# Lab6.net
KiCad netlist of a schematic drawn in EAGLE
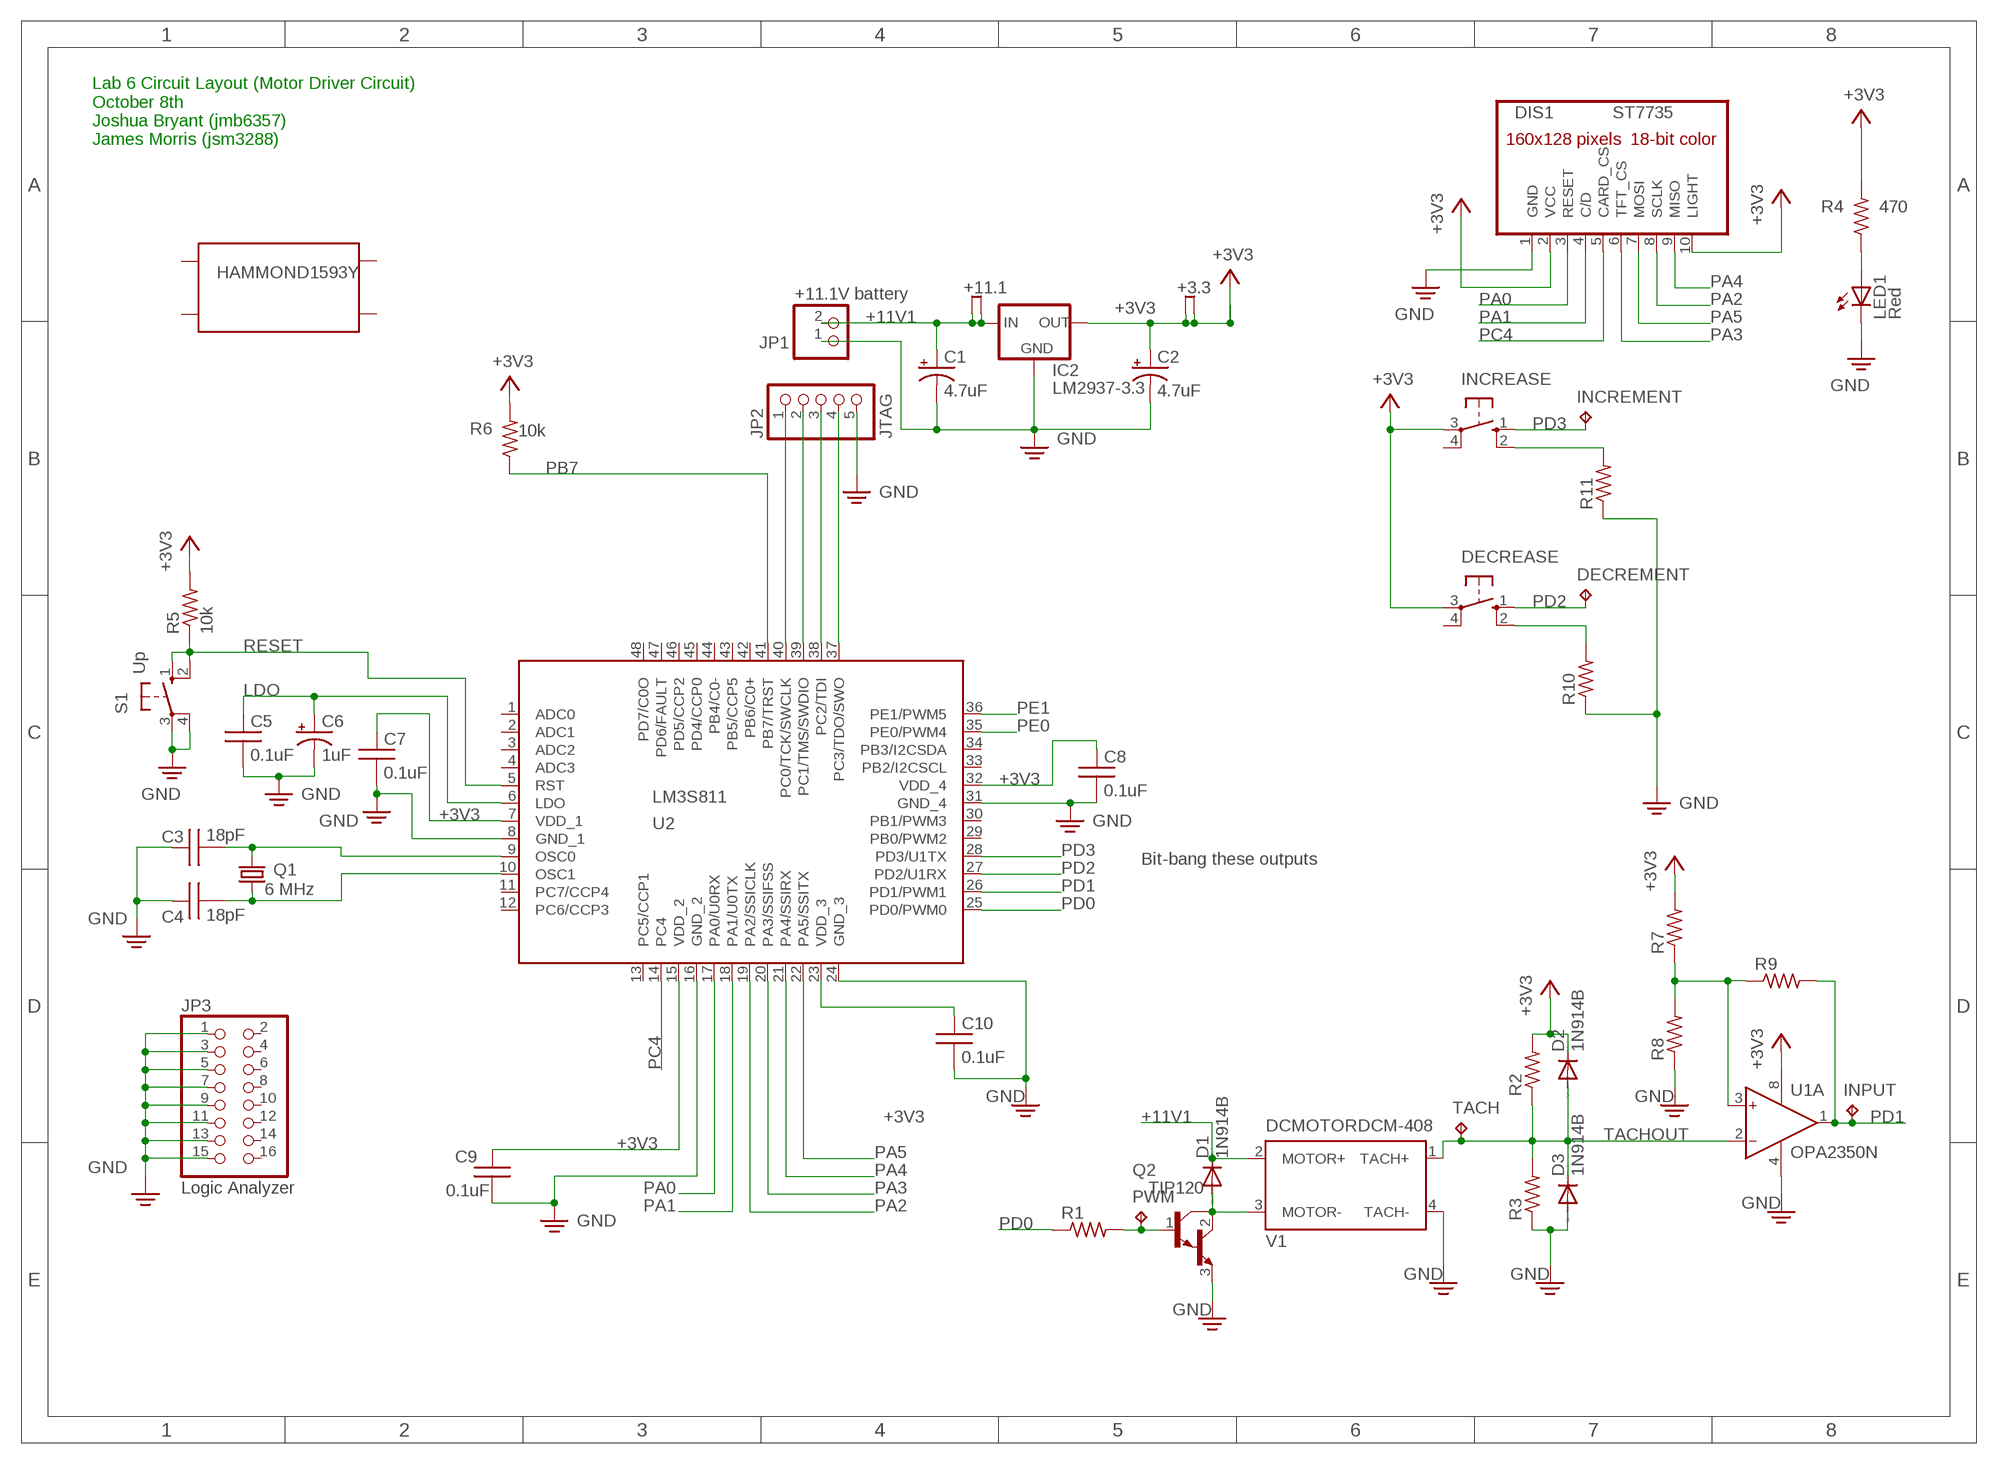
[diagram p0: schematic, sheet 1]

(export (version "E")
  (design (tool "Eeschema 10.0.6"))
  (components
    (comp (ref "+3.3")
      (value "TP2")
      (footprint "eagle-import:TP2")
      (libsource (lib "eagle-import") (part "TP2"))
    )
    (comp (ref "+11.1")
      (value "TP2")
      (footprint "eagle-import:TP2")
      (libsource (lib "eagle-import") (part "TP2"))
    )
    (comp (ref "C1")
      (value "4.7uF")
      (footprint "eagle-import:CAP200MILPOLARIZED")
      (libsource (lib "eagle-import") (part "CAPACITOR_POLARIZEDE5-6"))
    )
    (comp (ref "C2")
      (value "4.7uF")
      (footprint "eagle-import:CAP200MILPOLARIZED")
      (libsource (lib "eagle-import") (part "CAPACITOR_POLARIZEDE5-6"))
    )
    (comp (ref "C3")
      (value "18pF")
      (footprint "eagle-import:CAP100MIL")
      (libsource (lib "eagle-import") (part "CAPACITOR025-024X044"))
    )
    (comp (ref "C4")
      (value "18pF")
      (footprint "eagle-import:CAP100MIL")
      (libsource (lib "eagle-import") (part "CAPACITOR025-024X044"))
    )
    (comp (ref "C5")
      (value "0.1uF")
      (footprint "eagle-import:CAP100MIL")
      (libsource (lib "eagle-import") (part "CAPACITOR025-024X044"))
    )
    (comp (ref "C6")
      (value "1uF")
      (footprint "eagle-import:CAP200MILPOLARIZED")
      (libsource (lib "eagle-import") (part "CAPACITOR_POLARIZEDE5-6"))
    )
    (comp (ref "C7")
      (value "0.1uF")
      (footprint "eagle-import:CAP100MIL")
      (libsource (lib "eagle-import") (part "CAPACITOR025-024X044"))
    )
    (comp (ref "C8")
      (value "0.1uF")
      (footprint "eagle-import:CAP100MIL")
      (libsource (lib "eagle-import") (part "CAPACITOR025-024X044"))
    )
    (comp (ref "C9")
      (value "0.1uF")
      (footprint "eagle-import:CAP100MIL")
      (libsource (lib "eagle-import") (part "CAPACITOR025-024X044"))
    )
    (comp (ref "C10")
      (value "0.1uF")
      (footprint "eagle-import:CAP100MIL")
      (libsource (lib "eagle-import") (part "CAPACITOR025-024X044"))
    )
    (comp (ref "D1")
      (value "1N914B")
      (footprint "eagle-import:DO35-7")
      (libsource (lib "eagle-import") (part "1N914B"))
    )
    (comp (ref "D2")
      (value "1N914B")
      (footprint "eagle-import:DO35-7")
      (libsource (lib "eagle-import") (part "1N914B"))
    )
    (comp (ref "D3")
      (value "1N914B")
      (footprint "eagle-import:DO35-7")
      (libsource (lib "eagle-import") (part "1N914B"))
    )
    (comp (ref "DECREASE")
      (value "B3F-1052")
      (footprint "eagle-import:B3F-10XX")
      (fields (field (name "MPN") "B3F-1000"))
      (libsource (lib "eagle-import") (part "B3F-1052"))
    )
    (comp (ref "DECREMENT")
      (value "TP_KEYSTONE500X")
      (footprint "eagle-import:P1.1MM")
      (libsource (lib "eagle-import") (part "TP_KEYSTONE500X"))
    )
    (comp (ref "DIS1")
      (value "ST7735")
      (footprint "eagle-import:ST7735")
      (libsource (lib "eagle-import") (part "ST7735"))
    )
    (comp (ref "IC2")
      (value "LM2937-3.3")
      (footprint "eagle-import:78XXS")
      (libsource (lib "eagle-import") (part "78XXS"))
    )
    (comp (ref "INCREASE")
      (value "B3F-1052")
      (footprint "eagle-import:B3F-10XX")
      (fields (field (name "MPN") "B3F-1000"))
      (libsource (lib "eagle-import") (part "B3F-1052"))
    )
    (comp (ref "INCREMENT")
      (value "TP_KEYSTONE500X")
      (footprint "eagle-import:P1.1MM")
      (libsource (lib "eagle-import") (part "TP_KEYSTONE500X"))
    )
    (comp (ref "INPUT")
      (value "TP_KEYSTONE500X")
      (footprint "eagle-import:P1.1MM")
      (libsource (lib "eagle-import") (part "TP_KEYSTONE500X"))
    )
    (comp (ref "JP1")
      (value "+11.1V battery")
      (footprint "eagle-import:1X02")
      (libsource (lib "eagle-import") (part "PINHD-1X2"))
    )
    (comp (ref "JP2")
      (value "JTAG")
      (footprint "eagle-import:1X05")
      (libsource (lib "eagle-import") (part "PINHD-1X5"))
    )
    (comp (ref "JP3")
      (value "Logic Analyzer")
      (footprint "eagle-import:2X08_90")
      (libsource (lib "eagle-import") (part "PINHD-2X8/90"))
    )
    (comp (ref "LED1")
      (value "Red")
      (footprint "eagle-import:LED5MM")
      (libsource (lib "eagle-import") (part "LED5MM"))
    )
    (comp (ref "PWM")
      (value "TP_KEYSTONE500X")
      (footprint "eagle-import:P1.1MM")
      (libsource (lib "eagle-import") (part "TP_KEYSTONE500X"))
    )
    (comp (ref "Q1")
      (value "6 MHz")
      (footprint "eagle-import:HC49_S")
      (libsource (lib "eagle-import") (part "CRYSTALHC49S"))
    )
    (comp (ref "Q2")
      (value "TIP120")
      (footprint "eagle-import:TO220")
      (libsource (lib "eagle-import") (part "TIP120"))
    )
    (comp (ref "R1")
      (value "RESISTOR0204/7")
      (footprint "eagle-import:RES300MIL")
      (libsource (lib "eagle-import") (part "RESISTOR0204/7"))
    )
    (comp (ref "R2")
      (value "RESISTOR0204/7")
      (footprint "eagle-import:RES300MIL")
      (libsource (lib "eagle-import") (part "RESISTOR0204/7"))
    )
    (comp (ref "R3")
      (value "RESISTOR0204/7")
      (footprint "eagle-import:RES300MIL")
      (libsource (lib "eagle-import") (part "RESISTOR0204/7"))
    )
    (comp (ref "R4")
      (value "470")
      (footprint "eagle-import:RES200MIL")
      (libsource (lib "eagle-import") (part "RESISTOR0204/5"))
    )
    (comp (ref "R5")
      (value "10k")
      (footprint "eagle-import:RES200MIL")
      (libsource (lib "eagle-import") (part "RESISTOR0204/5"))
    )
    (comp (ref "R6")
      (value "10k")
      (footprint "eagle-import:RES200MIL")
      (libsource (lib "eagle-import") (part "RESISTOR0204/5"))
    )
    (comp (ref "R7")
      (value "RESISTOR0204/7")
      (footprint "eagle-import:RES300MIL")
      (libsource (lib "eagle-import") (part "RESISTOR0204/7"))
    )
    (comp (ref "R8")
      (value "RESISTOR0204/7")
      (footprint "eagle-import:RES300MIL")
      (libsource (lib "eagle-import") (part "RESISTOR0204/7"))
    )
    (comp (ref "R9")
      (value "RESISTOR0204/7")
      (footprint "eagle-import:RES300MIL")
      (libsource (lib "eagle-import") (part "RESISTOR0204/7"))
    )
    (comp (ref "R10")
      (value "RESISTOR0204/7")
      (footprint "eagle-import:RES300MIL")
      (libsource (lib "eagle-import") (part "RESISTOR0204/7"))
    )
    (comp (ref "R11")
      (value "RESISTOR0204/7")
      (footprint "eagle-import:RES300MIL")
      (libsource (lib "eagle-import") (part "RESISTOR0204/7"))
    )
    (comp (ref "S1")
      (value "Up")
      (footprint "eagle-import:B3F-10XX")
      (fields (field (name "MPN") "B3F-1000"))
      (libsource (lib "eagle-import") (part "B3F-1052"))
    )
    (comp (ref "TACH")
      (value "TP_KEYSTONE500X")
      (footprint "eagle-import:P1.1MM")
      (libsource (lib "eagle-import") (part "TP_KEYSTONE500X"))
    )
    (comp (ref "U$1")
      (value "HAMMOND1593Y")
      (footprint "eagle-import:HAMMOND1593Y")
      (libsource (lib "eagle-import") (part "HAMMOND1593Y"))
    )
    (comp (ref "U1")
      (value "OPA2350N")
      (footprint "eagle-import:DIL08")
      (libsource (lib "eagle-import") (part "OPA2350N"))
    )
    (comp (ref "U2")
      (value "LM3S811")
      (footprint "eagle-import:LQFP48-7X7")
      (libsource (lib "eagle-import") (part "LM3S811"))
    )
    (comp (ref "V1")
      (value "DCMOTORDCM-408")
      (footprint "eagle-import:DCMOTOR")
      (libsource (lib "eagle-import") (part "DCMOTORDCM-408"))
    )
  )
  (nets
    (net (code "1") (name "+3V3") (class "Default")
      (node (ref "+3.3") (pin "MP") (pinfunction "TPA_MP") (pintype "passive"))
      (node (ref "+3.3") (pin "MP1") (pinfunction "TPB_MP1") (pintype "passive"))
      (node (ref "C10") (pin "1") (pinfunction "1_1") (pintype "passive"))
      (node (ref "C2") (pin "+") (pinfunction "+_+") (pintype "passive"))
      (node (ref "C7") (pin "1") (pinfunction "1_1") (pintype "passive"))
      (node (ref "C8") (pin "1") (pinfunction "1_1") (pintype "passive"))
      (node (ref "C9") (pin "1") (pinfunction "1_1") (pintype "passive"))
      (node (ref "D2") (pin "C") (pinfunction "C_C") (pintype "passive"))
      (node (ref "DECREASE") (pin "3") (pinfunction "P_3") (pintype "passive"))
      (node (ref "DIS1") (pin "10") (pinfunction "LIGHT_10") (pintype "passive"))
      (node (ref "DIS1") (pin "2") (pinfunction "VCC_2") (pintype "power_in"))
      (node (ref "IC2") (pin "OUT") (pinfunction "OUT_OUT") (pintype "passive"))
      (node (ref "INCREASE") (pin "3") (pinfunction "P_3") (pintype "passive"))
      (node (ref "R2") (pin "2") (pinfunction "2_2") (pintype "passive"))
      (node (ref "R4") (pin "2") (pinfunction "2_2") (pintype "passive"))
      (node (ref "R5") (pin "2") (pinfunction "2_2") (pintype "passive"))
      (node (ref "R6") (pin "2") (pinfunction "2_2") (pintype "passive"))
      (node (ref "R7") (pin "2") (pinfunction "2_2") (pintype "passive"))
      (node (ref "U1") (pin "8") (pinfunction "V+_8") (pintype "power_in"))
      (node (ref "U2") (pin "15") (pinfunction "VDD_2_15") (pintype "power_in"))
      (node (ref "U2") (pin "23") (pinfunction "VDD_3_23") (pintype "power_in"))
      (node (ref "U2") (pin "32") (pinfunction "VDD_4_32") (pintype "power_in"))
      (node (ref "U2") (pin "7") (pinfunction "VDD_1_7") (pintype "power_in"))
    )
    (net (code "2") (name "/+11V1") (class "Default")
      (node (ref "+11.1") (pin "MP") (pinfunction "TPA_MP") (pintype "passive"))
      (node (ref "+11.1") (pin "MP1") (pinfunction "TPB_MP1") (pintype "passive"))
      (node (ref "C1") (pin "+") (pinfunction "+_+") (pintype "passive"))
      (node (ref "D1") (pin "C") (pinfunction "C_C") (pintype "passive"))
      (node (ref "IC2") (pin "IN") (pinfunction "IN_IN") (pintype "input"))
      (node (ref "JP1") (pin "2") (pinfunction "2_2") (pintype "passive"))
      (node (ref "V1") (pin "2") (pinfunction "MOTOR+_2") (pintype "passive"))
    )
    (net (code "3") (name "/LDO") (class "Default")
      (node (ref "C5") (pin "1") (pinfunction "1_1") (pintype "passive"))
      (node (ref "C6") (pin "+") (pinfunction "+_+") (pintype "passive"))
      (node (ref "U2") (pin "6") (pinfunction "LDO_6") (pintype "power_in"))
    )
    (net (code "4") (name "/PA0") (class "Default")
      (node (ref "DIS1") (pin "3") (pinfunction "RESET_3") (pintype "input"))
      (node (ref "U2") (pin "17") (pinfunction "PA0/U0RX_17") (pintype "bidirectional"))
    )
    (net (code "5") (name "/PA1") (class "Default")
      (node (ref "DIS1") (pin "4") (pinfunction "C/D_4") (pintype "input"))
      (node (ref "U2") (pin "18") (pinfunction "PA1/U0TX_18") (pintype "bidirectional"))
    )
    (net (code "6") (name "/PA2") (class "Default")
      (node (ref "DIS1") (pin "8") (pinfunction "SCLK_8") (pintype "input"))
      (node (ref "U2") (pin "19") (pinfunction "PA2/SSICLK_19") (pintype "bidirectional"))
    )
    (net (code "7") (name "/PA3") (class "Default")
      (node (ref "DIS1") (pin "6") (pinfunction "TFT_CS_6") (pintype "input"))
      (node (ref "U2") (pin "20") (pinfunction "PA3/SSIFSS_20") (pintype "bidirectional"))
    )
    (net (code "8") (name "/PA4") (class "Default")
      (node (ref "DIS1") (pin "9") (pinfunction "MISO_9") (pintype "output"))
      (node (ref "U2") (pin "21") (pinfunction "PA4/SSIRX_21") (pintype "bidirectional"))
    )
    (net (code "9") (name "/PA5") (class "Default")
      (node (ref "DIS1") (pin "7") (pinfunction "MOSI_7") (pintype "input"))
      (node (ref "U2") (pin "22") (pinfunction "PA5/SSITX_22") (pintype "bidirectional"))
    )
    (net (code "10") (name "/PB7") (class "Default")
      (node (ref "R6") (pin "1") (pinfunction "1_1") (pintype "passive"))
      (node (ref "U2") (pin "41") (pinfunction "PB7/TRST_41") (pintype "bidirectional"))
    )
    (net (code "11") (name "/PC4") (class "Default")
      (node (ref "DIS1") (pin "5") (pinfunction "CARD_CS_5") (pintype "input"))
      (node (ref "U2") (pin "14") (pinfunction "PC4_14") (pintype "bidirectional"))
    )
    (net (code "12") (name "/PD0") (class "Default")
      (node (ref "R1") (pin "1") (pinfunction "1_1") (pintype "passive"))
      (node (ref "U2") (pin "25") (pinfunction "PD0/PWM0_25") (pintype "bidirectional"))
    )
    (net (code "13") (name "/PD1") (class "Default")
      (node (ref "INPUT") (pin "TP") (pinfunction "TP_TP") (pintype "input"))
      (node (ref "R9") (pin "2") (pinfunction "2_2") (pintype "passive"))
      (node (ref "U1") (pin "1") (pinfunction "OUT_1") (pintype "output"))
      (node (ref "U2") (pin "26") (pinfunction "PD1/PWM1_26") (pintype "bidirectional"))
    )
    (net (code "14") (name "/PD2") (class "Default")
      (node (ref "DECREASE") (pin "1") (pinfunction "S_1") (pintype "passive"))
      (node (ref "DECREMENT") (pin "TP") (pinfunction "TP_TP") (pintype "input"))
      (node (ref "U2") (pin "27") (pinfunction "PD2/U1RX_27") (pintype "bidirectional"))
    )
    (net (code "15") (name "/PD3") (class "Default")
      (node (ref "INCREASE") (pin "1") (pinfunction "S_1") (pintype "passive"))
      (node (ref "INCREMENT") (pin "TP") (pinfunction "TP_TP") (pintype "input"))
      (node (ref "U2") (pin "28") (pinfunction "PD3/U1TX_28") (pintype "bidirectional"))
    )
    (net (code "16") (name "/PE0") (class "Default")
      (node (ref "U2") (pin "35") (pinfunction "PE0/PWM4_35") (pintype "bidirectional"))
    )
    (net (code "17") (name "/PE1") (class "Default")
      (node (ref "U2") (pin "36") (pinfunction "PE1/PWM5_36") (pintype "bidirectional"))
    )
    (net (code "18") (name "/RESET") (class "Default")
      (node (ref "R5") (pin "1") (pinfunction "1_1") (pintype "passive"))
      (node (ref "S1") (pin "1") (pinfunction "S_1") (pintype "passive"))
      (node (ref "S1") (pin "2") (pinfunction "S1_2") (pintype "passive"))
      (node (ref "U2") (pin "5") (pinfunction "RST_5") (pintype "input"))
    )
    (net (code "19") (name "/TACHOUT") (class "Default")
      (node (ref "D2") (pin "A") (pinfunction "A_A") (pintype "passive"))
      (node (ref "D3") (pin "C") (pinfunction "C_C") (pintype "passive"))
      (node (ref "R2") (pin "1") (pinfunction "1_1") (pintype "passive"))
      (node (ref "R3") (pin "2") (pinfunction "2_2") (pintype "passive"))
      (node (ref "TACH") (pin "TP") (pinfunction "TP_TP") (pintype "input"))
      (node (ref "U1") (pin "2") (pinfunction "IN-_2") (pintype "input"))
      (node (ref "V1") (pin "1") (pinfunction "TACH+_1") (pintype "passive"))
    )
    (net (code "20") (name "GND") (class "Default")
      (node (ref "C1") (pin "-") (pinfunction "-_-") (pintype "passive"))
      (node (ref "C10") (pin "2") (pinfunction "2_2") (pintype "passive"))
      (node (ref "C2") (pin "-") (pinfunction "-_-") (pintype "passive"))
      (node (ref "C3") (pin "1") (pinfunction "1_1") (pintype "passive"))
      (node (ref "C4") (pin "1") (pinfunction "1_1") (pintype "passive"))
      (node (ref "C5") (pin "2") (pinfunction "2_2") (pintype "passive"))
      (node (ref "C6") (pin "-") (pinfunction "-_-") (pintype "passive"))
      (node (ref "C7") (pin "2") (pinfunction "2_2") (pintype "passive"))
      (node (ref "C8") (pin "2") (pinfunction "2_2") (pintype "passive"))
      (node (ref "C9") (pin "2") (pinfunction "2_2") (pintype "passive"))
      (node (ref "D3") (pin "A") (pinfunction "A_A") (pintype "passive"))
      (node (ref "DIS1") (pin "1") (pinfunction "GND_1") (pintype "power_in"))
      (node (ref "IC2") (pin "GND") (pinfunction "GND_GND") (pintype "input"))
      (node (ref "JP1") (pin "1") (pinfunction "1_1") (pintype "passive"))
      (node (ref "JP2") (pin "5") (pinfunction "5_5") (pintype "passive"))
      (node (ref "JP3") (pin "1") (pinfunction "1_1") (pintype "passive"))
      (node (ref "JP3") (pin "11") (pinfunction "11_11") (pintype "passive"))
      (node (ref "JP3") (pin "13") (pinfunction "13_13") (pintype "passive"))
      (node (ref "JP3") (pin "15") (pinfunction "15_15") (pintype "passive"))
      (node (ref "JP3") (pin "3") (pinfunction "3_3") (pintype "passive"))
      (node (ref "JP3") (pin "5") (pinfunction "5_5") (pintype "passive"))
      (node (ref "JP3") (pin "7") (pinfunction "7_7") (pintype "passive"))
      (node (ref "JP3") (pin "9") (pinfunction "9_9") (pintype "passive"))
      (node (ref "LED1") (pin "K") (pinfunction "C_K") (pintype "passive"))
      (node (ref "Q2") (pin "3") (pinfunction "E_3") (pintype "passive"))
      (node (ref "R10") (pin "1") (pinfunction "1_1") (pintype "passive"))
      (node (ref "R11") (pin "1") (pinfunction "1_1") (pintype "passive"))
      (node (ref "R3") (pin "1") (pinfunction "1_1") (pintype "passive"))
      (node (ref "R8") (pin "1") (pinfunction "1_1") (pintype "passive"))
      (node (ref "S1") (pin "3") (pinfunction "P_3") (pintype "passive"))
      (node (ref "S1") (pin "4") (pinfunction "P1_4") (pintype "passive"))
      (node (ref "U1") (pin "4") (pinfunction "V-_4") (pintype "power_in"))
      (node (ref "U2") (pin "16") (pinfunction "GND_2_16") (pintype "power_in"))
      (node (ref "U2") (pin "24") (pinfunction "GND_3_24") (pintype "power_in"))
      (node (ref "U2") (pin "31") (pinfunction "GND_4_31") (pintype "power_in"))
      (node (ref "U2") (pin "8") (pinfunction "GND_1_8") (pintype "power_in"))
      (node (ref "V1") (pin "4") (pinfunction "TACH-_4") (pintype "passive"))
    )
    (net (code "21") (name "Net-(DECREASE-S1)") (class "Default")
      (node (ref "DECREASE") (pin "2") (pinfunction "S1_2") (pintype "passive"))
      (node (ref "R10") (pin "2") (pinfunction "2_2") (pintype "passive"))
    )
    (net (code "22") (name "Net-(INCREASE-S1)") (class "Default")
      (node (ref "INCREASE") (pin "2") (pinfunction "S1_2") (pintype "passive"))
      (node (ref "R11") (pin "2") (pinfunction "2_2") (pintype "passive"))
    )
    (net (code "23") (name "Net-(LED1-PadA)") (class "Default")
      (node (ref "LED1") (pin "A") (pinfunction "A_A") (pintype "passive"))
      (node (ref "R4") (pin "1") (pinfunction "1_1") (pintype "passive"))
    )
    (net (code "24") (name "Net-(Q2-B)") (class "Default")
      (node (ref "PWM") (pin "TP") (pinfunction "TP_TP") (pintype "input"))
      (node (ref "Q2") (pin "1") (pinfunction "B_1") (pintype "passive"))
      (node (ref "R1") (pin "2") (pinfunction "2_2") (pintype "passive"))
    )
    (net (code "25") (name "Net-(Q2-C)") (class "Default")
      (node (ref "D1") (pin "A") (pinfunction "A_A") (pintype "passive"))
      (node (ref "Q2") (pin "2") (pinfunction "C_2") (pintype "passive"))
      (node (ref "V1") (pin "3") (pinfunction "MOTOR-_3") (pintype "passive"))
    )
    (net (code "26") (name "Net-(U1A-IN+)") (class "Default")
      (node (ref "R7") (pin "1") (pinfunction "1_1") (pintype "passive"))
      (node (ref "R8") (pin "2") (pinfunction "2_2") (pintype "passive"))
      (node (ref "R9") (pin "1") (pinfunction "1_1") (pintype "passive"))
      (node (ref "U1") (pin "3") (pinfunction "IN+_3") (pintype "input"))
    )
    (net (code "27") (name "Net-(U2-OSC0)") (class "Default")
      (node (ref "C3") (pin "2") (pinfunction "2_2") (pintype "passive"))
      (node (ref "Q1") (pin "2") (pinfunction "2_2") (pintype "passive"))
      (node (ref "U2") (pin "9") (pinfunction "OSC0_9") (pintype "bidirectional"))
    )
    (net (code "28") (name "Net-(U2-OSC1)") (class "Default")
      (node (ref "C4") (pin "2") (pinfunction "2_2") (pintype "passive"))
      (node (ref "Q1") (pin "1") (pinfunction "1_1") (pintype "passive"))
      (node (ref "U2") (pin "10") (pinfunction "OSC1_10") (pintype "bidirectional"))
    )
    (net (code "29") (name "Net-(U2-PC0{slash}TCK{slash}SWCLK)") (class "Default")
      (node (ref "JP2") (pin "1") (pinfunction "1_1") (pintype "passive"))
      (node (ref "U2") (pin "40") (pinfunction "PC0/TCK/SWCLK_40") (pintype "bidirectional"))
    )
    (net (code "30") (name "Net-(U2-PC1{slash}TMS{slash}SWDIO)") (class "Default")
      (node (ref "JP2") (pin "2") (pinfunction "2_2") (pintype "passive"))
      (node (ref "U2") (pin "39") (pinfunction "PC1/TMS/SWDIO_39") (pintype "bidirectional"))
    )
    (net (code "31") (name "Net-(U2-PC2{slash}TDI)") (class "Default")
      (node (ref "JP2") (pin "3") (pinfunction "3_3") (pintype "passive"))
      (node (ref "U2") (pin "38") (pinfunction "PC2/TDI_38") (pintype "bidirectional"))
    )
    (net (code "32") (name "Net-(U2-PC3{slash}TDO{slash}SWO)") (class "Default")
      (node (ref "JP2") (pin "4") (pinfunction "4_4") (pintype "passive"))
      (node (ref "U2") (pin "37") (pinfunction "PC3/TDO/SWO_37") (pintype "bidirectional"))
    )
    (net (code "33") (name "unconnected-(DECREASE-P1-Pad4)") (class "Default")
      (node (ref "DECREASE") (pin "4") (pinfunction "P1_4") (pintype "passive"))
    )
    (net (code "34") (name "unconnected-(INCREASE-P1-Pad4)") (class "Default")
      (node (ref "INCREASE") (pin "4") (pinfunction "P1_4") (pintype "passive"))
    )
    (net (code "35") (name "unconnected-(JP3-Pad2)") (class "Default")
      (node (ref "JP3") (pin "2") (pinfunction "2_2") (pintype "passive"))
    )
    (net (code "36") (name "unconnected-(JP3-Pad4)") (class "Default")
      (node (ref "JP3") (pin "4") (pinfunction "4_4") (pintype "passive"))
    )
    (net (code "37") (name "unconnected-(JP3-Pad6)") (class "Default")
      (node (ref "JP3") (pin "6") (pinfunction "6_6") (pintype "passive"))
    )
    (net (code "38") (name "unconnected-(JP3-Pad8)") (class "Default")
      (node (ref "JP3") (pin "8") (pinfunction "8_8") (pintype "passive"))
    )
    (net (code "39") (name "unconnected-(JP3-Pad10)") (class "Default")
      (node (ref "JP3") (pin "10") (pinfunction "10_10") (pintype "passive"))
    )
    (net (code "40") (name "unconnected-(JP3-Pad12)") (class "Default")
      (node (ref "JP3") (pin "12") (pinfunction "12_12") (pintype "passive"))
    )
    (net (code "41") (name "unconnected-(JP3-Pad14)") (class "Default")
      (node (ref "JP3") (pin "14") (pinfunction "14_14") (pintype "passive"))
    )
    (net (code "42") (name "unconnected-(JP3-Pad16)") (class "Default")
      (node (ref "JP3") (pin "16") (pinfunction "16_16") (pintype "passive"))
    )
    (net (code "43") (name "unconnected-(U$1-H0-Pad1)") (class "Default")
      (node (ref "U$1") (pin "1") (pinfunction "H0_1") (pintype "passive"))
    )
    (net (code "44") (name "unconnected-(U$1-H1-Pad2)") (class "Default")
      (node (ref "U$1") (pin "2") (pinfunction "H1_2") (pintype "passive"))
    )
    (net (code "45") (name "unconnected-(U$1-H2-Pad3)") (class "Default")
      (node (ref "U$1") (pin "3") (pinfunction "H2_3") (pintype "passive"))
    )
    (net (code "46") (name "unconnected-(U$1-H3-Pad4)") (class "Default")
      (node (ref "U$1") (pin "4") (pinfunction "H3_4") (pintype "passive"))
    )
    (net (code "47") (name "unconnected-(U2-ADC0-Pad1)") (class "Default")
      (node (ref "U2") (pin "1") (pinfunction "ADC0_1") (pintype "input"))
    )
    (net (code "48") (name "unconnected-(U2-ADC1-Pad2)") (class "Default")
      (node (ref "U2") (pin "2") (pinfunction "ADC1_2") (pintype "input"))
    )
    (net (code "49") (name "unconnected-(U2-ADC2-Pad3)") (class "Default")
      (node (ref "U2") (pin "3") (pinfunction "ADC2_3") (pintype "input"))
    )
    (net (code "50") (name "unconnected-(U2-ADC3-Pad4)") (class "Default")
      (node (ref "U2") (pin "4") (pinfunction "ADC3_4") (pintype "input"))
    )
    (net (code "51") (name "unconnected-(U2-PB0{slash}PWM2-Pad29)") (class "Default")
      (node (ref "U2") (pin "29") (pinfunction "PB0/PWM2_29") (pintype "bidirectional"))
    )
    (net (code "52") (name "unconnected-(U2-PB1{slash}PWM3-Pad30)") (class "Default")
      (node (ref "U2") (pin "30") (pinfunction "PB1/PWM3_30") (pintype "bidirectional"))
    )
    (net (code "53") (name "unconnected-(U2-PB2{slash}I2CSCL-Pad33)") (class "Default")
      (node (ref "U2") (pin "33") (pinfunction "PB2/I2CSCL_33") (pintype "bidirectional"))
    )
    (net (code "54") (name "unconnected-(U2-PB3{slash}I2CSDA-Pad34)") (class "Default")
      (node (ref "U2") (pin "34") (pinfunction "PB3/I2CSDA_34") (pintype "bidirectional"))
    )
    (net (code "55") (name "unconnected-(U2-PB4{slash}C0--Pad44)") (class "Default")
      (node (ref "U2") (pin "44") (pinfunction "PB4/C0-_44") (pintype "bidirectional"))
    )
    (net (code "56") (name "unconnected-(U2-PB5{slash}CCP5-Pad43)") (class "Default")
      (node (ref "U2") (pin "43") (pinfunction "PB5/CCP5_43") (pintype "bidirectional"))
    )
    (net (code "57") (name "unconnected-(U2-PB6{slash}C0+-Pad42)") (class "Default")
      (node (ref "U2") (pin "42") (pinfunction "PB6/C0+_42") (pintype "bidirectional"))
    )
    (net (code "58") (name "unconnected-(U2-PC5{slash}CCP1-Pad13)") (class "Default")
      (node (ref "U2") (pin "13") (pinfunction "PC5/CCP1_13") (pintype "bidirectional"))
    )
    (net (code "59") (name "unconnected-(U2-PC6{slash}CCP3-Pad12)") (class "Default")
      (node (ref "U2") (pin "12") (pinfunction "PC6/CCP3_12") (pintype "bidirectional"))
    )
    (net (code "60") (name "unconnected-(U2-PC7{slash}CCP4-Pad11)") (class "Default")
      (node (ref "U2") (pin "11") (pinfunction "PC7/CCP4_11") (pintype "bidirectional"))
    )
    (net (code "61") (name "unconnected-(U2-PD4{slash}CCP0-Pad45)") (class "Default")
      (node (ref "U2") (pin "45") (pinfunction "PD4/CCP0_45") (pintype "bidirectional"))
    )
    (net (code "62") (name "unconnected-(U2-PD5{slash}CCP2-Pad46)") (class "Default")
      (node (ref "U2") (pin "46") (pinfunction "PD5/CCP2_46") (pintype "bidirectional"))
    )
    (net (code "63") (name "unconnected-(U2-PD6{slash}FAULT-Pad47)") (class "Default")
      (node (ref "U2") (pin "47") (pinfunction "PD6/FAULT_47") (pintype "bidirectional"))
    )
    (net (code "64") (name "unconnected-(U2-PD7{slash}C0O-Pad48)") (class "Default")
      (node (ref "U2") (pin "48") (pinfunction "PD7/C0O_48") (pintype "bidirectional"))
    )
  )
)
